# 3P4W_v1p3.net
KiCad netlist of a schematic drawn in EAGLE
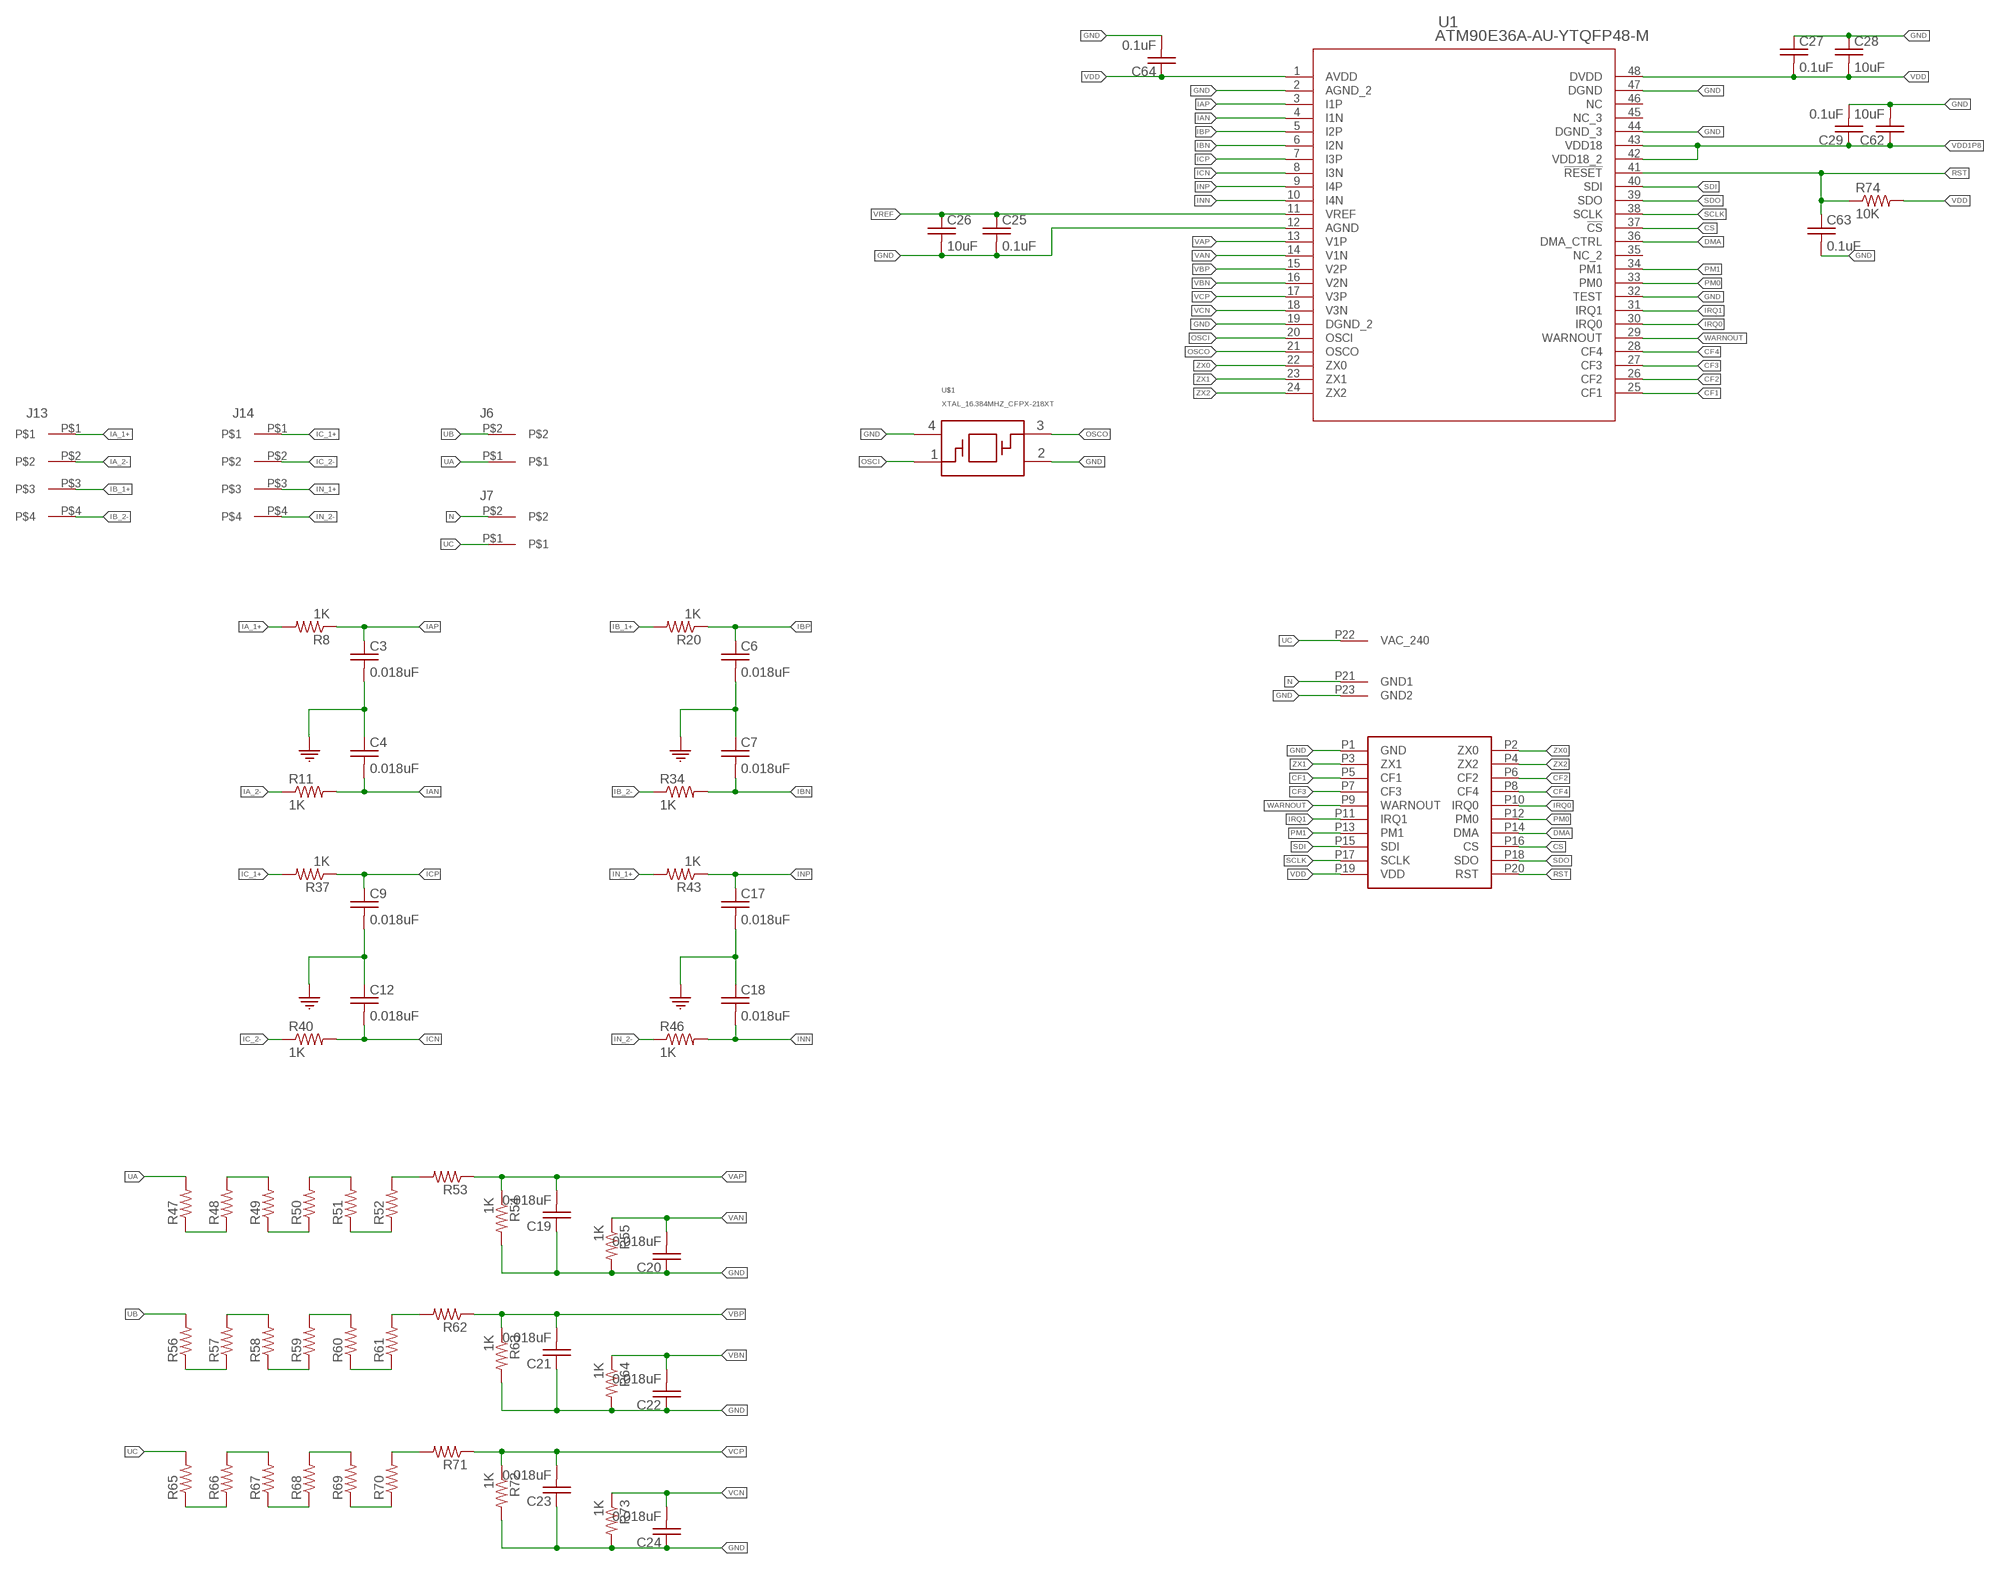
[diagram p0: schematic, sheet 1]

(export (version "E")
  (design (tool "Eeschema 10.0.6"))
  (components
    (comp (ref "C3")
      (value "0.018uF")
      (footprint "eagle-import:0402")
      (libsource (lib "eagle-import") (part "C_0402"))
    )
    (comp (ref "C4")
      (value "0.018uF")
      (footprint "eagle-import:0402")
      (libsource (lib "eagle-import") (part "C_0402"))
    )
    (comp (ref "C6")
      (value "0.018uF")
      (footprint "eagle-import:0402")
      (libsource (lib "eagle-import") (part "C_0402"))
    )
    (comp (ref "C7")
      (value "0.018uF")
      (footprint "eagle-import:0402")
      (libsource (lib "eagle-import") (part "C_0402"))
    )
    (comp (ref "C9")
      (value "0.018uF")
      (footprint "eagle-import:0402")
      (libsource (lib "eagle-import") (part "C_0402"))
    )
    (comp (ref "C12")
      (value "0.018uF")
      (footprint "eagle-import:0402")
      (libsource (lib "eagle-import") (part "C_0402"))
    )
    (comp (ref "C17")
      (value "0.018uF")
      (footprint "eagle-import:0402")
      (libsource (lib "eagle-import") (part "C_0402"))
    )
    (comp (ref "C18")
      (value "0.018uF")
      (footprint "eagle-import:0402")
      (libsource (lib "eagle-import") (part "C_0402"))
    )
    (comp (ref "C19")
      (value "0.018uF")
      (footprint "eagle-import:0402")
      (libsource (lib "eagle-import") (part "C_0402"))
    )
    (comp (ref "C20")
      (value "0.018uF")
      (footprint "eagle-import:0402")
      (libsource (lib "eagle-import") (part "C_0402"))
    )
    (comp (ref "C21")
      (value "0.018uF")
      (footprint "eagle-import:0402")
      (libsource (lib "eagle-import") (part "C_0402"))
    )
    (comp (ref "C22")
      (value "0.018uF")
      (footprint "eagle-import:0402")
      (libsource (lib "eagle-import") (part "C_0402"))
    )
    (comp (ref "C23")
      (value "0.018uF")
      (footprint "eagle-import:0402")
      (libsource (lib "eagle-import") (part "C_0402"))
    )
    (comp (ref "C24")
      (value "0.018uF")
      (footprint "eagle-import:0402")
      (libsource (lib "eagle-import") (part "C_0402"))
    )
    (comp (ref "C25")
      (value "0.1uF")
      (footprint "eagle-import:0402")
      (libsource (lib "eagle-import") (part "C_0402"))
    )
    (comp (ref "C26")
      (value "10uF")
      (footprint "eagle-import:0402")
      (libsource (lib "eagle-import") (part "C_0402"))
    )
    (comp (ref "C27")
      (value "0.1uF")
      (footprint "eagle-import:0402")
      (libsource (lib "eagle-import") (part "C_0402"))
    )
    (comp (ref "C28")
      (value "10uF")
      (footprint "eagle-import:0402")
      (libsource (lib "eagle-import") (part "C_0402"))
    )
    (comp (ref "C29")
      (value "0.1uF")
      (footprint "eagle-import:0402")
      (libsource (lib "eagle-import") (part "C_0402"))
    )
    (comp (ref "C62")
      (value "10uF")
      (footprint "eagle-import:0402")
      (libsource (lib "eagle-import") (part "C_0402"))
    )
    (comp (ref "C63")
      (value "0.1uF")
      (footprint "eagle-import:0402")
      (libsource (lib "eagle-import") (part "C_0402"))
    )
    (comp (ref "C64")
      (value "0.1uF")
      (footprint "eagle-import:0402")
      (libsource (lib "eagle-import") (part "C_0402"))
    )
    (comp (ref "J6")
      (value "3.81MM_1_X_2_RT_ANGLE_PLUG_HEADER")
      (footprint "eagle-import:2_3.81MM_PITCH")
      (libsource (lib "eagle-import") (part "3.81MM_1_X_2_RT_ANGLE_PLUG_HEADER"))
    )
    (comp (ref "J7")
      (value "3.81MM_1_X_2_RT_ANGLE_PLUG_HEADER")
      (footprint "eagle-import:2_3.81MM_PITCH")
      (libsource (lib "eagle-import") (part "3.81MM_1_X_2_RT_ANGLE_PLUG_HEADER"))
    )
    (comp (ref "J13")
      (value "3.81MM_1_X_4_RT_ANGLE_PLUG_HEADER")
      (footprint "eagle-import:1X4_3.81MM_PITCH")
      (libsource (lib "eagle-import") (part "3.81MM_1_X_4_RT_ANGLE_PLUG_HEADER"))
    )
    (comp (ref "J14")
      (value "3.81MM_1_X_4_RT_ANGLE_PLUG_HEADER")
      (footprint "eagle-import:1X4_3.81MM_PITCH")
      (libsource (lib "eagle-import") (part "3.81MM_1_X_4_RT_ANGLE_PLUG_HEADER"))
    )
    (comp (ref "R8")
      (value "1K")
      (footprint "eagle-import:0402")
      (libsource (lib "eagle-import") (part "R_0402"))
    )
    (comp (ref "R11")
      (value "1K")
      (footprint "eagle-import:0402")
      (libsource (lib "eagle-import") (part "R_0402"))
    )
    (comp (ref "R20")
      (value "1K")
      (footprint "eagle-import:0402")
      (libsource (lib "eagle-import") (part "R_0402"))
    )
    (comp (ref "R34")
      (value "1K")
      (footprint "eagle-import:0402")
      (libsource (lib "eagle-import") (part "R_0402"))
    )
    (comp (ref "R37")
      (value "1K")
      (footprint "eagle-import:0402")
      (libsource (lib "eagle-import") (part "R_0402"))
    )
    (comp (ref "R40")
      (value "1K")
      (footprint "eagle-import:0402")
      (libsource (lib "eagle-import") (part "R_0402"))
    )
    (comp (ref "R43")
      (value "1K")
      (footprint "eagle-import:0402")
      (libsource (lib "eagle-import") (part "R_0402"))
    )
    (comp (ref "R46")
      (value "1K")
      (footprint "eagle-import:0402")
      (libsource (lib "eagle-import") (part "R_0402"))
    )
    (comp (ref "R47")
      (value "R_0402")
      (footprint "eagle-import:0402")
      (libsource (lib "eagle-import") (part "R_0402"))
    )
    (comp (ref "R48")
      (value "R_0402")
      (footprint "eagle-import:0402")
      (libsource (lib "eagle-import") (part "R_0402"))
    )
    (comp (ref "R49")
      (value "R_0402")
      (footprint "eagle-import:0402")
      (libsource (lib "eagle-import") (part "R_0402"))
    )
    (comp (ref "R50")
      (value "R_0402")
      (footprint "eagle-import:0402")
      (libsource (lib "eagle-import") (part "R_0402"))
    )
    (comp (ref "R51")
      (value "R_0402")
      (footprint "eagle-import:0402")
      (libsource (lib "eagle-import") (part "R_0402"))
    )
    (comp (ref "R52")
      (value "R_0402")
      (footprint "eagle-import:0402")
      (libsource (lib "eagle-import") (part "R_0402"))
    )
    (comp (ref "R53")
      (value "R_0402")
      (footprint "eagle-import:0402")
      (libsource (lib "eagle-import") (part "R_0402"))
    )
    (comp (ref "R54")
      (value "1K")
      (footprint "eagle-import:0402")
      (libsource (lib "eagle-import") (part "R_0402"))
    )
    (comp (ref "R55")
      (value "1K")
      (footprint "eagle-import:0402")
      (libsource (lib "eagle-import") (part "R_0402"))
    )
    (comp (ref "R56")
      (value "R_0402")
      (footprint "eagle-import:0402")
      (libsource (lib "eagle-import") (part "R_0402"))
    )
    (comp (ref "R57")
      (value "R_0402")
      (footprint "eagle-import:0402")
      (libsource (lib "eagle-import") (part "R_0402"))
    )
    (comp (ref "R58")
      (value "R_0402")
      (footprint "eagle-import:0402")
      (libsource (lib "eagle-import") (part "R_0402"))
    )
    (comp (ref "R59")
      (value "R_0402")
      (footprint "eagle-import:0402")
      (libsource (lib "eagle-import") (part "R_0402"))
    )
    (comp (ref "R60")
      (value "R_0402")
      (footprint "eagle-import:0402")
      (libsource (lib "eagle-import") (part "R_0402"))
    )
    (comp (ref "R61")
      (value "R_0402")
      (footprint "eagle-import:0402")
      (libsource (lib "eagle-import") (part "R_0402"))
    )
    (comp (ref "R62")
      (value "R_0402")
      (footprint "eagle-import:0402")
      (libsource (lib "eagle-import") (part "R_0402"))
    )
    (comp (ref "R63")
      (value "1K")
      (footprint "eagle-import:0402")
      (libsource (lib "eagle-import") (part "R_0402"))
    )
    (comp (ref "R64")
      (value "1K")
      (footprint "eagle-import:0402")
      (libsource (lib "eagle-import") (part "R_0402"))
    )
    (comp (ref "R65")
      (value "R_0402")
      (footprint "eagle-import:0402")
      (libsource (lib "eagle-import") (part "R_0402"))
    )
    (comp (ref "R66")
      (value "R_0402")
      (footprint "eagle-import:0402")
      (libsource (lib "eagle-import") (part "R_0402"))
    )
    (comp (ref "R67")
      (value "R_0402")
      (footprint "eagle-import:0402")
      (libsource (lib "eagle-import") (part "R_0402"))
    )
    (comp (ref "R68")
      (value "R_0402")
      (footprint "eagle-import:0402")
      (libsource (lib "eagle-import") (part "R_0402"))
    )
    (comp (ref "R69")
      (value "R_0402")
      (footprint "eagle-import:0402")
      (libsource (lib "eagle-import") (part "R_0402"))
    )
    (comp (ref "R70")
      (value "R_0402")
      (footprint "eagle-import:0402")
      (libsource (lib "eagle-import") (part "R_0402"))
    )
    (comp (ref "R71")
      (value "R_0402")
      (footprint "eagle-import:0402")
      (libsource (lib "eagle-import") (part "R_0402"))
    )
    (comp (ref "R72")
      (value "1K")
      (footprint "eagle-import:0402")
      (libsource (lib "eagle-import") (part "R_0402"))
    )
    (comp (ref "R73")
      (value "1K")
      (footprint "eagle-import:0402")
      (libsource (lib "eagle-import") (part "R_0402"))
    )
    (comp (ref "R74")
      (value "10K")
      (footprint "eagle-import:0402")
      (libsource (lib "eagle-import") (part "R_0402"))
    )
    (comp (ref "U$1")
      (value "XTAL_16.384MHZ_CFPX-218XT")
      (footprint "eagle-import:XTAL_2.5X2.0")
      (libsource (lib "eagle-import") (part "XTAL_16.384MHZ_CFPX-218XT"))
    )
    (comp (ref "U$2")
      (value "METER_BASE")
      (footprint "eagle-import:METER_BASE")
      (libsource (lib "eagle-import") (part "METER_BASE"))
    )
    (comp (ref "U1")
      (value "ATM90E36A-AU-YTQFP48-M")
      (footprint "eagle-import:TQFP48-M")
      (fields (field (name "MANUFACTURER_PART_NUMBER") "ATM90E36AAUY"))
      (libsource (lib "eagle-import") (part "ATM90E36A-AU-YTQFP48-M"))
    )
  )
  (nets
    (net (code "1") (name "CF1") (class "Default")
      (node (ref "U$2") (pin "P5") (pinfunction "CF1_P5") (pintype "bidirectional"))
      (node (ref "U1") (pin "25") (pinfunction "CF1_25") (pintype "output"))
    )
    (net (code "2") (name "CF2") (class "Default")
      (node (ref "U$2") (pin "P6") (pinfunction "CF2_P6") (pintype "bidirectional"))
      (node (ref "U1") (pin "26") (pinfunction "CF2_26") (pintype "output"))
    )
    (net (code "3") (name "CF3") (class "Default")
      (node (ref "U$2") (pin "P7") (pinfunction "CF3_P7") (pintype "bidirectional"))
      (node (ref "U1") (pin "27") (pinfunction "CF3_27") (pintype "output"))
    )
    (net (code "4") (name "CF4") (class "Default")
      (node (ref "U$2") (pin "P8") (pinfunction "CF4_P8") (pintype "bidirectional"))
      (node (ref "U1") (pin "28") (pinfunction "CF4_28") (pintype "output"))
    )
    (net (code "5") (name "CS") (class "Default")
      (node (ref "U$2") (pin "P16") (pinfunction "CS_P16") (pintype "bidirectional"))
      (node (ref "U1") (pin "37") (pinfunction "~{CS}_37") (pintype "bidirectional"))
    )
    (net (code "6") (name "DMA") (class "Default")
      (node (ref "U$2") (pin "P14") (pinfunction "DMA_P14") (pintype "bidirectional"))
      (node (ref "U1") (pin "36") (pinfunction "DMA_CTRL_36") (pintype "input"))
    )
    (net (code "7") (name "GND") (class "Default")
      (node (ref "C12") (pin "P$1") (pinfunction "1_P$1") (pintype "passive"))
      (node (ref "C17") (pin "P$2") (pinfunction "2_P$2") (pintype "passive"))
      (node (ref "C18") (pin "P$1") (pinfunction "1_P$1") (pintype "passive"))
      (node (ref "C19") (pin "P$1") (pinfunction "1_P$1") (pintype "passive"))
      (node (ref "C20") (pin "P$1") (pinfunction "1_P$1") (pintype "passive"))
      (node (ref "C21") (pin "P$1") (pinfunction "1_P$1") (pintype "passive"))
      (node (ref "C22") (pin "P$1") (pinfunction "1_P$1") (pintype "passive"))
      (node (ref "C23") (pin "P$1") (pinfunction "1_P$1") (pintype "passive"))
      (node (ref "C24") (pin "P$1") (pinfunction "1_P$1") (pintype "passive"))
      (node (ref "C25") (pin "P$2") (pinfunction "2_P$2") (pintype "passive"))
      (node (ref "C26") (pin "P$2") (pinfunction "2_P$2") (pintype "passive"))
      (node (ref "C27") (pin "P$1") (pinfunction "1_P$1") (pintype "passive"))
      (node (ref "C28") (pin "P$1") (pinfunction "1_P$1") (pintype "passive"))
      (node (ref "C29") (pin "P$2") (pinfunction "2_P$2") (pintype "passive"))
      (node (ref "C3") (pin "P$2") (pinfunction "2_P$2") (pintype "passive"))
      (node (ref "C4") (pin "P$1") (pinfunction "1_P$1") (pintype "passive"))
      (node (ref "C6") (pin "P$2") (pinfunction "2_P$2") (pintype "passive"))
      (node (ref "C62") (pin "P$2") (pinfunction "2_P$2") (pintype "passive"))
      (node (ref "C63") (pin "P$2") (pinfunction "2_P$2") (pintype "passive"))
      (node (ref "C64") (pin "P$2") (pinfunction "2_P$2") (pintype "passive"))
      (node (ref "C7") (pin "P$1") (pinfunction "1_P$1") (pintype "passive"))
      (node (ref "C9") (pin "P$2") (pinfunction "2_P$2") (pintype "passive"))
      (node (ref "R54") (pin "P$2") (pinfunction "2_P$2") (pintype "passive"))
      (node (ref "R55") (pin "P$2") (pinfunction "2_P$2") (pintype "passive"))
      (node (ref "R63") (pin "P$2") (pinfunction "2_P$2") (pintype "passive"))
      (node (ref "R64") (pin "P$2") (pinfunction "2_P$2") (pintype "passive"))
      (node (ref "R72") (pin "P$2") (pinfunction "2_P$2") (pintype "passive"))
      (node (ref "R73") (pin "P$2") (pinfunction "2_P$2") (pintype "passive"))
      (node (ref "U$1") (pin "2") (pinfunction "2_2") (pintype "bidirectional"))
      (node (ref "U$1") (pin "4") (pinfunction "4_4") (pintype "bidirectional"))
      (node (ref "U$2") (pin "P1") (pinfunction "GND_P1") (pintype "bidirectional"))
      (node (ref "U$2") (pin "P23") (pinfunction "GND2_P23") (pintype "bidirectional"))
      (node (ref "U1") (pin "12") (pinfunction "AGND_12") (pintype "power_in"))
      (node (ref "U1") (pin "19") (pinfunction "DGND_2_19") (pintype "power_in"))
      (node (ref "U1") (pin "2") (pinfunction "AGND_2_2") (pintype "power_in"))
      (node (ref "U1") (pin "32") (pinfunction "TEST_32") (pintype "input"))
      (node (ref "U1") (pin "44") (pinfunction "DGND_3_44") (pintype "power_in"))
      (node (ref "U1") (pin "47") (pinfunction "DGND_47") (pintype "power_in"))
    )
    (net (code "8") (name "IAN") (class "Default")
      (node (ref "C4") (pin "P$2") (pinfunction "2_P$2") (pintype "passive"))
      (node (ref "R11") (pin "P$2") (pinfunction "2_P$2") (pintype "passive"))
      (node (ref "U1") (pin "4") (pinfunction "I1N_4") (pintype "input"))
    )
    (net (code "9") (name "IAP") (class "Default")
      (node (ref "C3") (pin "P$1") (pinfunction "1_P$1") (pintype "passive"))
      (node (ref "R8") (pin "P$1") (pinfunction "1_P$1") (pintype "passive"))
      (node (ref "U1") (pin "3") (pinfunction "I1P_3") (pintype "input"))
    )
    (net (code "10") (name "IA_1+") (class "Default")
      (node (ref "J13") (pin "P$1") (pinfunction "P$1_P$1") (pintype "bidirectional"))
      (node (ref "R8") (pin "P$2") (pinfunction "2_P$2") (pintype "passive"))
    )
    (net (code "11") (name "IA_2-") (class "Default")
      (node (ref "J13") (pin "P$2") (pinfunction "P$2_P$2") (pintype "bidirectional"))
      (node (ref "R11") (pin "P$1") (pinfunction "1_P$1") (pintype "passive"))
    )
    (net (code "12") (name "IBN") (class "Default")
      (node (ref "C7") (pin "P$2") (pinfunction "2_P$2") (pintype "passive"))
      (node (ref "R34") (pin "P$2") (pinfunction "2_P$2") (pintype "passive"))
      (node (ref "U1") (pin "6") (pinfunction "I2N_6") (pintype "input"))
    )
    (net (code "13") (name "IBP") (class "Default")
      (node (ref "C6") (pin "P$1") (pinfunction "1_P$1") (pintype "passive"))
      (node (ref "R20") (pin "P$1") (pinfunction "1_P$1") (pintype "passive"))
      (node (ref "U1") (pin "5") (pinfunction "I2P_5") (pintype "input"))
    )
    (net (code "14") (name "IB_1+") (class "Default")
      (node (ref "J13") (pin "P$3") (pinfunction "P$3_P$3") (pintype "bidirectional"))
      (node (ref "R20") (pin "P$2") (pinfunction "2_P$2") (pintype "passive"))
    )
    (net (code "15") (name "IB_2-") (class "Default")
      (node (ref "J13") (pin "P$4") (pinfunction "P$4_P$4") (pintype "bidirectional"))
      (node (ref "R34") (pin "P$1") (pinfunction "1_P$1") (pintype "passive"))
    )
    (net (code "16") (name "ICN") (class "Default")
      (node (ref "C12") (pin "P$2") (pinfunction "2_P$2") (pintype "passive"))
      (node (ref "R40") (pin "P$2") (pinfunction "2_P$2") (pintype "passive"))
      (node (ref "U1") (pin "8") (pinfunction "I3N_8") (pintype "input"))
    )
    (net (code "17") (name "ICP") (class "Default")
      (node (ref "C9") (pin "P$1") (pinfunction "1_P$1") (pintype "passive"))
      (node (ref "R37") (pin "P$1") (pinfunction "1_P$1") (pintype "passive"))
      (node (ref "U1") (pin "7") (pinfunction "I3P_7") (pintype "input"))
    )
    (net (code "18") (name "IC_1+") (class "Default")
      (node (ref "J14") (pin "P$1") (pinfunction "P$1_P$1") (pintype "bidirectional"))
      (node (ref "R37") (pin "P$2") (pinfunction "2_P$2") (pintype "passive"))
    )
    (net (code "19") (name "IC_2-") (class "Default")
      (node (ref "J14") (pin "P$2") (pinfunction "P$2_P$2") (pintype "bidirectional"))
      (node (ref "R40") (pin "P$1") (pinfunction "1_P$1") (pintype "passive"))
    )
    (net (code "20") (name "INN") (class "Default")
      (node (ref "C18") (pin "P$2") (pinfunction "2_P$2") (pintype "passive"))
      (node (ref "R46") (pin "P$2") (pinfunction "2_P$2") (pintype "passive"))
      (node (ref "U1") (pin "10") (pinfunction "I4N_10") (pintype "input"))
    )
    (net (code "21") (name "INP") (class "Default")
      (node (ref "C17") (pin "P$1") (pinfunction "1_P$1") (pintype "passive"))
      (node (ref "R43") (pin "P$1") (pinfunction "1_P$1") (pintype "passive"))
      (node (ref "U1") (pin "9") (pinfunction "I4P_9") (pintype "input"))
    )
    (net (code "22") (name "IN_1+") (class "Default")
      (node (ref "J14") (pin "P$3") (pinfunction "P$3_P$3") (pintype "bidirectional"))
      (node (ref "R43") (pin "P$2") (pinfunction "2_P$2") (pintype "passive"))
    )
    (net (code "23") (name "IN_2-") (class "Default")
      (node (ref "J14") (pin "P$4") (pinfunction "P$4_P$4") (pintype "bidirectional"))
      (node (ref "R46") (pin "P$1") (pinfunction "1_P$1") (pintype "passive"))
    )
    (net (code "24") (name "IRQ0") (class "Default")
      (node (ref "U$2") (pin "P10") (pinfunction "IRQ0_P10") (pintype "bidirectional"))
      (node (ref "U1") (pin "30") (pinfunction "IRQ0_30") (pintype "output"))
    )
    (net (code "25") (name "IRQ1") (class "Default")
      (node (ref "U$2") (pin "P11") (pinfunction "IRQ1_P11") (pintype "bidirectional"))
      (node (ref "U1") (pin "31") (pinfunction "IRQ1_31") (pintype "output"))
    )
    (net (code "26") (name "N") (class "Default")
      (node (ref "J7") (pin "P$2") (pinfunction "P$2_P$2") (pintype "bidirectional"))
      (node (ref "U$2") (pin "P21") (pinfunction "GND1_P21") (pintype "bidirectional"))
    )
    (net (code "27") (name "Net-(R47-1)") (class "Default")
      (node (ref "R47") (pin "P$1") (pinfunction "1_P$1") (pintype "passive"))
      (node (ref "R48") (pin "P$1") (pinfunction "1_P$1") (pintype "passive"))
    )
    (net (code "28") (name "Net-(R48-2)") (class "Default")
      (node (ref "R48") (pin "P$2") (pinfunction "2_P$2") (pintype "passive"))
      (node (ref "R49") (pin "P$2") (pinfunction "2_P$2") (pintype "passive"))
    )
    (net (code "29") (name "Net-(R49-1)") (class "Default")
      (node (ref "R49") (pin "P$1") (pinfunction "1_P$1") (pintype "passive"))
      (node (ref "R50") (pin "P$1") (pinfunction "1_P$1") (pintype "passive"))
    )
    (net (code "30") (name "Net-(R50-2)") (class "Default")
      (node (ref "R50") (pin "P$2") (pinfunction "2_P$2") (pintype "passive"))
      (node (ref "R51") (pin "P$2") (pinfunction "2_P$2") (pintype "passive"))
    )
    (net (code "31") (name "Net-(R51-1)") (class "Default")
      (node (ref "R51") (pin "P$1") (pinfunction "1_P$1") (pintype "passive"))
      (node (ref "R52") (pin "P$1") (pinfunction "1_P$1") (pintype "passive"))
    )
    (net (code "32") (name "Net-(R52-2)") (class "Default")
      (node (ref "R52") (pin "P$2") (pinfunction "2_P$2") (pintype "passive"))
      (node (ref "R53") (pin "P$2") (pinfunction "2_P$2") (pintype "passive"))
    )
    (net (code "33") (name "Net-(R56-1)") (class "Default")
      (node (ref "R56") (pin "P$1") (pinfunction "1_P$1") (pintype "passive"))
      (node (ref "R57") (pin "P$1") (pinfunction "1_P$1") (pintype "passive"))
    )
    (net (code "34") (name "Net-(R57-2)") (class "Default")
      (node (ref "R57") (pin "P$2") (pinfunction "2_P$2") (pintype "passive"))
      (node (ref "R58") (pin "P$2") (pinfunction "2_P$2") (pintype "passive"))
    )
    (net (code "35") (name "Net-(R58-1)") (class "Default")
      (node (ref "R58") (pin "P$1") (pinfunction "1_P$1") (pintype "passive"))
      (node (ref "R59") (pin "P$1") (pinfunction "1_P$1") (pintype "passive"))
    )
    (net (code "36") (name "Net-(R59-2)") (class "Default")
      (node (ref "R59") (pin "P$2") (pinfunction "2_P$2") (pintype "passive"))
      (node (ref "R60") (pin "P$2") (pinfunction "2_P$2") (pintype "passive"))
    )
    (net (code "37") (name "Net-(R60-1)") (class "Default")
      (node (ref "R60") (pin "P$1") (pinfunction "1_P$1") (pintype "passive"))
      (node (ref "R61") (pin "P$1") (pinfunction "1_P$1") (pintype "passive"))
    )
    (net (code "38") (name "Net-(R61-2)") (class "Default")
      (node (ref "R61") (pin "P$2") (pinfunction "2_P$2") (pintype "passive"))
      (node (ref "R62") (pin "P$2") (pinfunction "2_P$2") (pintype "passive"))
    )
    (net (code "39") (name "Net-(R65-1)") (class "Default")
      (node (ref "R65") (pin "P$1") (pinfunction "1_P$1") (pintype "passive"))
      (node (ref "R66") (pin "P$1") (pinfunction "1_P$1") (pintype "passive"))
    )
    (net (code "40") (name "Net-(R66-2)") (class "Default")
      (node (ref "R66") (pin "P$2") (pinfunction "2_P$2") (pintype "passive"))
      (node (ref "R67") (pin "P$2") (pinfunction "2_P$2") (pintype "passive"))
    )
    (net (code "41") (name "Net-(R67-1)") (class "Default")
      (node (ref "R67") (pin "P$1") (pinfunction "1_P$1") (pintype "passive"))
      (node (ref "R68") (pin "P$1") (pinfunction "1_P$1") (pintype "passive"))
    )
    (net (code "42") (name "Net-(R68-2)") (class "Default")
      (node (ref "R68") (pin "P$2") (pinfunction "2_P$2") (pintype "passive"))
      (node (ref "R69") (pin "P$2") (pinfunction "2_P$2") (pintype "passive"))
    )
    (net (code "43") (name "Net-(R69-1)") (class "Default")
      (node (ref "R69") (pin "P$1") (pinfunction "1_P$1") (pintype "passive"))
      (node (ref "R70") (pin "P$1") (pinfunction "1_P$1") (pintype "passive"))
    )
    (net (code "44") (name "Net-(R70-2)") (class "Default")
      (node (ref "R70") (pin "P$2") (pinfunction "2_P$2") (pintype "passive"))
      (node (ref "R71") (pin "P$2") (pinfunction "2_P$2") (pintype "passive"))
    )
    (net (code "45") (name "OSCI") (class "Default")
      (node (ref "U$1") (pin "1") (pinfunction "1_1") (pintype "bidirectional"))
      (node (ref "U1") (pin "20") (pinfunction "OSCI_20") (pintype "input"))
    )
    (net (code "46") (name "OSCO") (class "Default")
      (node (ref "U$1") (pin "3") (pinfunction "3_3") (pintype "bidirectional"))
      (node (ref "U1") (pin "21") (pinfunction "OSCO_21") (pintype "output"))
    )
    (net (code "47") (name "PM0") (class "Default")
      (node (ref "U$2") (pin "P12") (pinfunction "PM0_P12") (pintype "bidirectional"))
      (node (ref "U1") (pin "33") (pinfunction "PM0_33") (pintype "input"))
    )
    (net (code "48") (name "PM1") (class "Default")
      (node (ref "U$2") (pin "P13") (pinfunction "PM1_P13") (pintype "bidirectional"))
      (node (ref "U1") (pin "34") (pinfunction "PM1_34") (pintype "input"))
    )
    (net (code "49") (name "RST") (class "Default")
      (node (ref "C63") (pin "P$1") (pinfunction "1_P$1") (pintype "passive"))
      (node (ref "R74") (pin "P$1") (pinfunction "1_P$1") (pintype "passive"))
      (node (ref "U$2") (pin "P20") (pinfunction "RST_P20") (pintype "bidirectional"))
      (node (ref "U1") (pin "41") (pinfunction "~{RESET}_41") (pintype "input"))
    )
    (net (code "50") (name "SCLK") (class "Default")
      (node (ref "U$2") (pin "P17") (pinfunction "SCLK_P17") (pintype "bidirectional"))
      (node (ref "U1") (pin "38") (pinfunction "SCLK_38") (pintype "bidirectional"))
    )
    (net (code "51") (name "SDI") (class "Default")
      (node (ref "U$2") (pin "P15") (pinfunction "SDI_P15") (pintype "bidirectional"))
      (node (ref "U1") (pin "40") (pinfunction "SDI_40") (pintype "bidirectional"))
    )
    (net (code "52") (name "SDO") (class "Default")
      (node (ref "U$2") (pin "P18") (pinfunction "SDO_P18") (pintype "bidirectional"))
      (node (ref "U1") (pin "39") (pinfunction "SDO_39") (pintype "bidirectional"))
    )
    (net (code "53") (name "UA") (class "Default")
      (node (ref "J6") (pin "P$1") (pinfunction "P$1_P$1") (pintype "bidirectional"))
      (node (ref "R47") (pin "P$2") (pinfunction "2_P$2") (pintype "passive"))
    )
    (net (code "54") (name "UB") (class "Default")
      (node (ref "J6") (pin "P$2") (pinfunction "P$2_P$2") (pintype "bidirectional"))
      (node (ref "R56") (pin "P$2") (pinfunction "2_P$2") (pintype "passive"))
    )
    (net (code "55") (name "UC") (class "Default")
      (node (ref "J7") (pin "P$1") (pinfunction "P$1_P$1") (pintype "bidirectional"))
      (node (ref "R65") (pin "P$2") (pinfunction "2_P$2") (pintype "passive"))
      (node (ref "U$2") (pin "P22") (pinfunction "VAC_240_P22") (pintype "bidirectional"))
    )
    (net (code "56") (name "VAN") (class "Default")
      (node (ref "C20") (pin "P$2") (pinfunction "2_P$2") (pintype "passive"))
      (node (ref "R55") (pin "P$1") (pinfunction "1_P$1") (pintype "passive"))
      (node (ref "U1") (pin "14") (pinfunction "V1N_14") (pintype "input"))
    )
    (net (code "57") (name "VAP") (class "Default")
      (node (ref "C19") (pin "P$2") (pinfunction "2_P$2") (pintype "passive"))
      (node (ref "R53") (pin "P$1") (pinfunction "1_P$1") (pintype "passive"))
      (node (ref "R54") (pin "P$1") (pinfunction "1_P$1") (pintype "passive"))
      (node (ref "U1") (pin "13") (pinfunction "V1P_13") (pintype "input"))
    )
    (net (code "58") (name "VBN") (class "Default")
      (node (ref "C22") (pin "P$2") (pinfunction "2_P$2") (pintype "passive"))
      (node (ref "R64") (pin "P$1") (pinfunction "1_P$1") (pintype "passive"))
      (node (ref "U1") (pin "16") (pinfunction "V2N_16") (pintype "input"))
    )
    (net (code "59") (name "VBP") (class "Default")
      (node (ref "C21") (pin "P$2") (pinfunction "2_P$2") (pintype "passive"))
      (node (ref "R62") (pin "P$1") (pinfunction "1_P$1") (pintype "passive"))
      (node (ref "R63") (pin "P$1") (pinfunction "1_P$1") (pintype "passive"))
      (node (ref "U1") (pin "15") (pinfunction "V2P_15") (pintype "input"))
    )
    (net (code "60") (name "VCN") (class "Default")
      (node (ref "C24") (pin "P$2") (pinfunction "2_P$2") (pintype "passive"))
      (node (ref "R73") (pin "P$1") (pinfunction "1_P$1") (pintype "passive"))
      (node (ref "U1") (pin "18") (pinfunction "V3N_18") (pintype "input"))
    )
    (net (code "61") (name "VCP") (class "Default")
      (node (ref "C23") (pin "P$2") (pinfunction "2_P$2") (pintype "passive"))
      (node (ref "R71") (pin "P$1") (pinfunction "1_P$1") (pintype "passive"))
      (node (ref "R72") (pin "P$1") (pinfunction "1_P$1") (pintype "passive"))
      (node (ref "U1") (pin "17") (pinfunction "V3P_17") (pintype "input"))
    )
    (net (code "62") (name "VDD") (class "Default")
      (node (ref "C27") (pin "P$2") (pinfunction "2_P$2") (pintype "passive"))
      (node (ref "C28") (pin "P$2") (pinfunction "2_P$2") (pintype "passive"))
      (node (ref "C64") (pin "P$1") (pinfunction "1_P$1") (pintype "passive"))
      (node (ref "R74") (pin "P$2") (pinfunction "2_P$2") (pintype "passive"))
      (node (ref "U$2") (pin "P19") (pinfunction "VDD_P19") (pintype "bidirectional"))
      (node (ref "U1") (pin "1") (pinfunction "AVDD_1") (pintype "power_in"))
      (node (ref "U1") (pin "48") (pinfunction "DVDD_48") (pintype "power_in"))
    )
    (net (code "63") (name "VDD1P8") (class "Default")
      (node (ref "C29") (pin "P$1") (pinfunction "1_P$1") (pintype "passive"))
      (node (ref "C62") (pin "P$1") (pinfunction "1_P$1") (pintype "passive"))
      (node (ref "U1") (pin "42") (pinfunction "VDD18_2_42") (pintype "power_in"))
      (node (ref "U1") (pin "43") (pinfunction "VDD18_43") (pintype "power_in"))
    )
    (net (code "64") (name "VREF") (class "Default")
      (node (ref "C25") (pin "P$1") (pinfunction "1_P$1") (pintype "passive"))
      (node (ref "C26") (pin "P$1") (pinfunction "1_P$1") (pintype "passive"))
      (node (ref "U1") (pin "11") (pinfunction "VREF_11") (pintype "output"))
    )
    (net (code "65") (name "WARNOUT") (class "Default")
      (node (ref "U$2") (pin "P9") (pinfunction "WARNOUT_P9") (pintype "bidirectional"))
      (node (ref "U1") (pin "29") (pinfunction "WARNOUT_29") (pintype "output"))
    )
    (net (code "66") (name "ZX0") (class "Default")
      (node (ref "U$2") (pin "P2") (pinfunction "ZX0_P2") (pintype "bidirectional"))
      (node (ref "U1") (pin "22") (pinfunction "ZX0_22") (pintype "output"))
    )
    (net (code "67") (name "ZX1") (class "Default")
      (node (ref "U$2") (pin "P3") (pinfunction "ZX1_P3") (pintype "bidirectional"))
      (node (ref "U1") (pin "23") (pinfunction "ZX1_23") (pintype "output"))
    )
    (net (code "68") (name "ZX2") (class "Default")
      (node (ref "U$2") (pin "P4") (pinfunction "ZX2_P4") (pintype "bidirectional"))
      (node (ref "U1") (pin "24") (pinfunction "ZX2_24") (pintype "output"))
    )
    (net (code "69") (name "unconnected-(U1-NC-Pad46)") (class "Default")
      (node (ref "U1") (pin "46") (pinfunction "NC_46") (pintype "no_connect"))
    )
    (net (code "70") (name "unconnected-(U1-NC_2-Pad35)") (class "Default")
      (node (ref "U1") (pin "35") (pinfunction "NC_2_35") (pintype "no_connect"))
    )
    (net (code "71") (name "unconnected-(U1-NC_3-Pad45)") (class "Default")
      (node (ref "U1") (pin "45") (pinfunction "NC_3_45") (pintype "no_connect"))
    )
  )
)
